# Hackster.net
KiCad netlist of a schematic drawn in Altium Designer
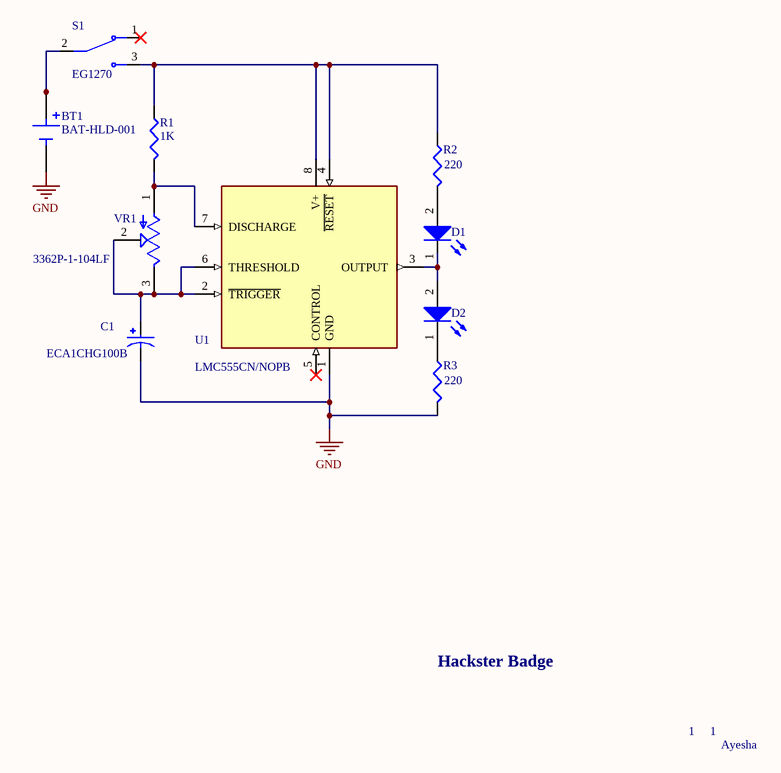
[diagram p0: Hackster.SchDoc]

(export (version "E")
  (design (tool "Eeschema 10.0.6"))
  (components
    (comp (ref "BT1")
      (value "BAT-HLD-001")
      (footprint "BAT_BAT-HLD-001")
      (description "Battery Retainer Coin, 20.0mm 1 Cell SMD (SMT) Tab")
      (libsource (lib "BAT-HLD-001") (part "BAT-HLD-001"))
    )
    (comp (ref "C1")
      (value "ECA1CHG100B")
      (footprint "CAPPRD500W50D500H1100")
      (description "Cap Aluminum Lytic 10uF 16V 20% (5 X 11mm) Radial 5mm 31mA 1000h 105C Automotive Ammo")
      (fields (field (name "MF") "Panasonic Electronic") (field (name "MP") "ECA-1CHG100B"))
      (libsource (lib "ECA1CHG100B") (part "ECA1CHG100B"))
    )
    (comp (ref "D1")
      (value "Blue, 2.8V, 30°")
      (footprint "WL-TMRW_D3.9H10.5")
      (description "WL-TMRW Mono-color Round Waterclear, THT, D3.9 x H10.5mm, Blue, 2.8V, 30°")
      (fields
        (field (name "MANUFACTURER PART NUMBER") "151033BS03000")
        (field (name "MANUFACTURER") "Wurth Elektronik")
      )
      (libsource (lib "WL-TMRW") (part "151033BS03000"))
    )
    (comp (ref "D2")
      (value "Blue, 2.8V, 30°")
      (footprint "WL-TMRW_D3.9H10.5")
      (description "WL-TMRW Mono-color Round Waterclear, THT, D3.9 x H10.5mm, Blue, 2.8V, 30°")
      (fields
        (field (name "MANUFACTURER PART NUMBER") "151033BS03000")
        (field (name "MANUFACTURER") "Wurth Elektronik")
      )
      (libsource (lib "WL-TMRW") (part "151033BS03000"))
    )
    (comp (ref "R1")
      (value "1K")
      (footprint "RESAD1100W55L680D260")
      (description "Resistor")
      (libsource (lib "Tortuga") (part "Res"))
    )
    (comp (ref "R2")
      (value "220")
      (footprint "RESAD1100W55L680D260")
      (description "Resistor")
      (libsource (lib "Tortuga") (part "Res"))
    )
    (comp (ref "R3")
      (value "220")
      (footprint "RESAD1100W55L680D260")
      (description "Resistor")
      (libsource (lib "Tortuga") (part "Res"))
    )
    (comp (ref "S1")
      (value "EG1270")
      (footprint "SW_SS312SAH4-R")
      (description "Slide Switch SPDT Through Hole, Right Angle")
      (fields (field (name "MF") "E-Switch"))
      (libsource (lib "EG1270") (part "EG1270"))
    )
    (comp (ref "U1")
      (value "LMC555CN/NOPB")
      (footprint "DIP794W45P254L959H508Q8")
      (description "Worldâ€™s smallest 555 timer with low power, high accuracy and a Fmax of 3MHz")
      (fields (field (name "MF") "Texas Instruments"))
      (libsource (lib "LMC555CN_NOPB") (part "LMC555CN/NOPB"))
    )
    (comp (ref "VR1")
      (value "3362P-1-104LF")
      (footprint "TRIM_3362P-1-104LF")
      (fields (field (name "MF") "Bourns Electronics") (field (name "MP") "3362P1104LF"))
      (libsource (lib "3362P-1-104LF") (part "3362P-1-104LF"))
    )
  )
  (nets
    (net (code "1") (name "GND") (class "Default")
      (node (ref "BT1") (pin "N1") (pinfunction "NEG_N1") (pintype "passive"))
      (node (ref "C1") (pin "N") (pinfunction "N_N") (pintype "passive"))
      (node (ref "R3") (pin "2") (pinfunction "2_2") (pintype "passive"))
      (node (ref "U1") (pin "1") (pinfunction "GND_1") (pintype "power_in"))
    )
    (net (code "2") (name "Net-(BT1-POS-PadP1)") (class "Default")
      (node (ref "BT1") (pin "P1") (pinfunction "POS_P1") (pintype "passive"))
      (node (ref "BT1") (pin "P2") (pinfunction "POS_P2") (pintype "passive"))
      (node (ref "S1") (pin "2") (pinfunction "2_2") (pintype "passive"))
    )
    (net (code "3") (name "Net-(D1-A)") (class "Default")
      (node (ref "D1") (pin "2") (pinfunction "A_2") (pintype "passive"))
      (node (ref "R2") (pin "2") (pinfunction "2_2") (pintype "passive"))
    )
    (net (code "4") (name "Net-(D1-K)") (class "Default")
      (node (ref "D1") (pin "1") (pinfunction "K_1") (pintype "passive"))
      (node (ref "D2") (pin "2") (pinfunction "A_2") (pintype "passive"))
      (node (ref "U1") (pin "3") (pinfunction "OUTPUT_3") (pintype "output"))
    )
    (net (code "5") (name "Net-(D2-K)") (class "Default")
      (node (ref "D2") (pin "1") (pinfunction "K_1") (pintype "passive"))
      (node (ref "R3") (pin "1") (pinfunction "1_1") (pintype "passive"))
    )
    (net (code "6") (name "Net-(U1-DISCHARGE)") (class "Default")
      (node (ref "R1") (pin "2") (pinfunction "2_2") (pintype "passive"))
      (node (ref "U1") (pin "7") (pinfunction "DISCHARGE_7") (pintype "input"))
      (node (ref "VR1") (pin "1") (pinfunction "CCW_1") (pintype "passive"))
    )
    (net (code "7") (name "Net-(U1-THRESHOLD)") (class "Default")
      (node (ref "C1") (pin "P") (pinfunction "P_P") (pintype "passive"))
      (node (ref "U1") (pin "2") (pinfunction "~{TRIGGER}_2") (pintype "input"))
      (node (ref "U1") (pin "6") (pinfunction "THRESHOLD_6") (pintype "input"))
      (node (ref "VR1") (pin "2") (pinfunction "WIPER_2") (pintype "passive"))
      (node (ref "VR1") (pin "3") (pinfunction "CW_3") (pintype "passive"))
    )
    (net (code "8") (name "Net-(U1-V+)") (class "Default")
      (node (ref "R1") (pin "1") (pinfunction "1_1") (pintype "passive"))
      (node (ref "R2") (pin "1") (pinfunction "1_1") (pintype "passive"))
      (node (ref "S1") (pin "3") (pinfunction "3_3") (pintype "passive"))
      (node (ref "U1") (pin "4") (pinfunction "~{RESET}_4") (pintype "input"))
      (node (ref "U1") (pin "8") (pinfunction "V+_8") (pintype "power_in"))
    )
    (net (code "9") (name "unconnected-(S1-Pad1)") (class "Default")
      (node (ref "S1") (pin "1") (pinfunction "1_1") (pintype "passive+no_connect"))
    )
    (net (code "10") (name "unconnected-(U1-CONTROL-Pad5)") (class "Default")
      (node (ref "U1") (pin "5") (pinfunction "CONTROL_5") (pintype "input+no_connect"))
    )
  )
)
